# Analog_Sensors.net
KiCad netlist of a schematic drawn in Altium Designer
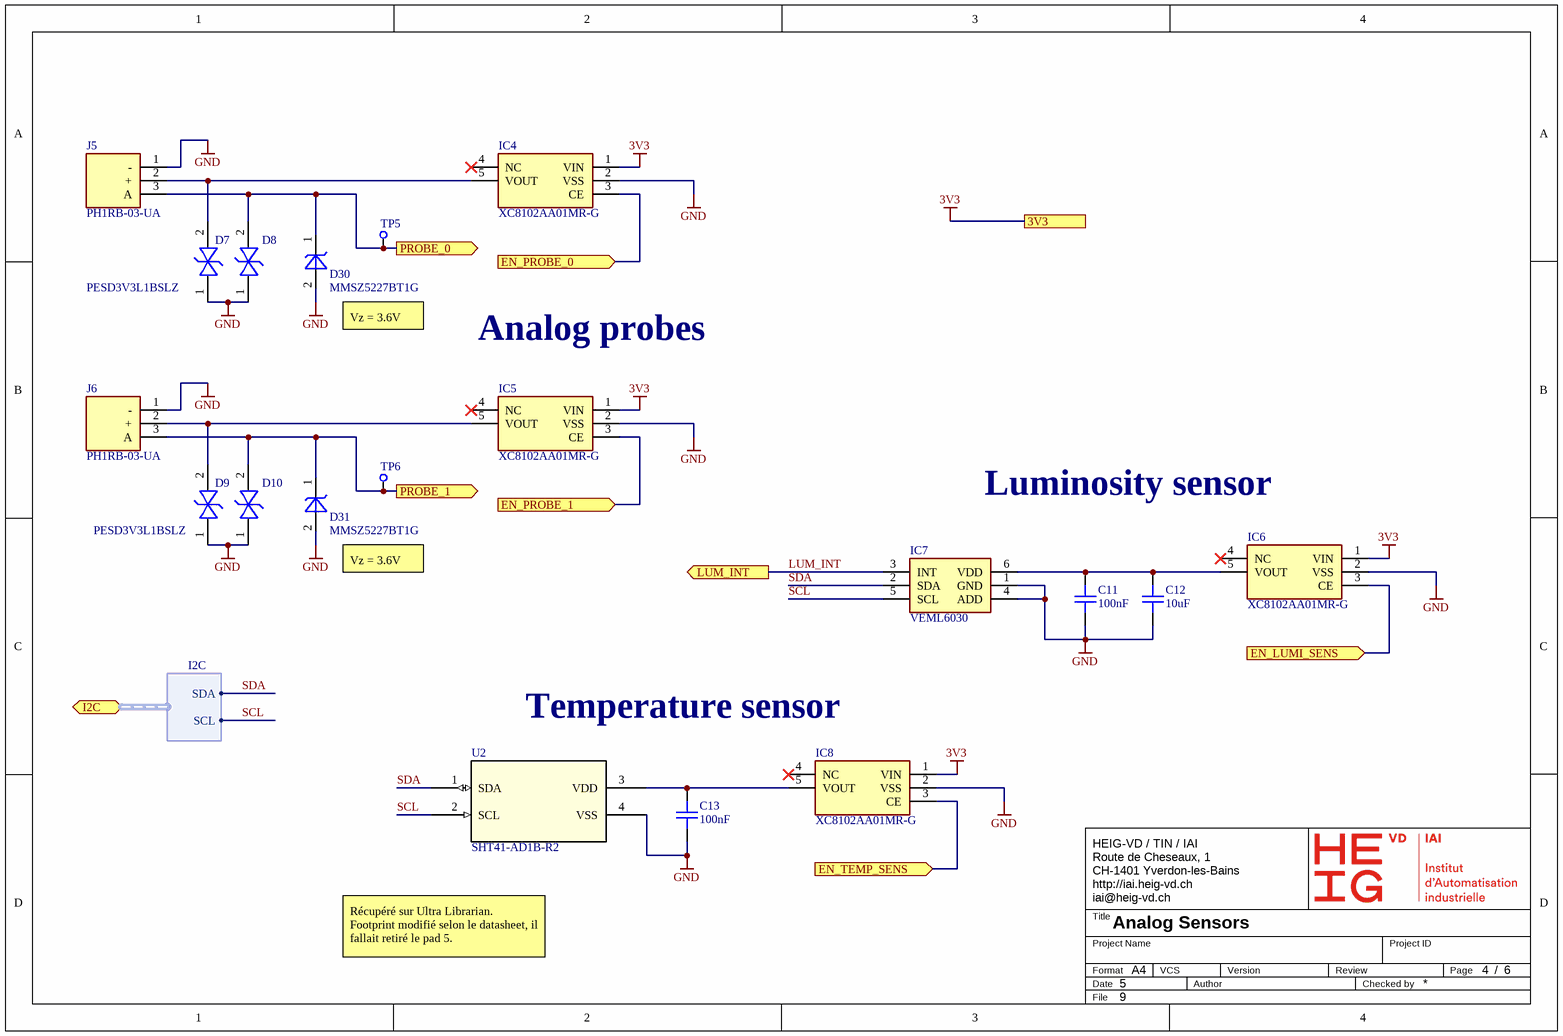
[diagram p0: Analog_Sensors.SchDoc]

(export (version "E")
  (design (tool "Eeschema 10.0.6"))
  (components
    (comp (ref "C11")
      (value "100nF")
      (footprint "CAPC1005X05N")
      (description "100nF 10% 50V Ceramic Capacitor X8L 0402 (1005 Metric)")
      (fields (field (name "TOLERANCE") "10%"))
      (libsource (lib "HEIG-VD Pro") (part "Capacitor"))
    )
    (comp (ref "C12")
      (value "10uF")
      (footprint "CAPC3216X18N")
      (description "10 µF ±10% 50V Ceramic Capacitor X7R 1206 (3216 Metric)")
      (fields (field (name "TOLERANCE") "10%"))
      (libsource (lib "HEIG-VD Pro") (part "Capacitor"))
    )
    (comp (ref "C13")
      (value "100nF")
      (footprint "CAPC1005X05N")
      (description "100nF 10% 50V Ceramic Capacitor X8L 0402 (1005 Metric)")
      (fields (field (name "TOLERANCE") "10%"))
      (libsource (lib "HEIG-VD Pro") (part "Capacitor"))
    )
    (comp (ref "D7")
      (value "PESD3V3L1BSLZ")
      (footprint "PESD3V3L1BSLZ")
      (description "Diode ESD (Bi-directional)")
      (fields (field (name "MOUSER PART NUMBER") "771-PESD3V3L1BSLZ"))
      (libsource (lib "Rainette") (part "PESD3V3L1BSLZ"))
    )
    (comp (ref "D8")
      (value "PESD3V3L1BSLZ")
      (footprint "PESD3V3L1BSLZ")
      (description "Diode ESD (Bi-directional)")
      (fields (field (name "MOUSER PART NUMBER") "771-PESD3V3L1BSLZ"))
      (libsource (lib "Rainette") (part "PESD3V3L1BSLZ"))
    )
    (comp (ref "D9")
      (value "PESD3V3L1BSLZ")
      (footprint "PESD3V3L1BSLZ")
      (description "Diode ESD (Bi-directional)")
      (fields (field (name "MOUSER PART NUMBER") "771-PESD3V3L1BSLZ"))
      (libsource (lib "Rainette") (part "PESD3V3L1BSLZ"))
    )
    (comp (ref "D10")
      (value "PESD3V3L1BSLZ")
      (footprint "PESD3V3L1BSLZ")
      (description "Diode ESD (Bi-directional)")
      (fields (field (name "MOUSER PART NUMBER") "771-PESD3V3L1BSLZ"))
      (libsource (lib "Rainette") (part "PESD3V3L1BSLZ"))
    )
    (comp (ref "D30")
      (value "MMSZ5227BT1G")
      (footprint "SOD3717X135")
      (description "Zener Diode 3.6V 500 mW ±5% Surface Mount SOD-123")
      (fields (field (name "POWER") "500mW") (field (name "TOLERANCE") "5%"))
      (libsource (lib "HEIG-VD iAi") (part "Diode Zener"))
    )
    (comp (ref "D31")
      (value "MMSZ5227BT1G")
      (footprint "SOD3717X135")
      (description "Zener Diode 3.6V 500 mW ±5% Surface Mount SOD-123")
      (fields (field (name "POWER") "500mW") (field (name "TOLERANCE") "5%"))
      (libsource (lib "HEIG-VD iAi") (part "Diode Zener"))
    )
    (comp (ref "IC4")
      (value "XC8102AA01MR-G")
      (footprint "SOT95P280X130-5N")
      (description "Integrated Circuit")
      (fields (field (name "MOUSER PART NUMBER") "865-XC8102AA01MR-G"))
      (libsource (lib "Rainette") (part "XC8102AA01MR-G"))
    )
    (comp (ref "IC5")
      (value "XC8102AA01MR-G")
      (footprint "SOT95P280X130-5N")
      (description "Integrated Circuit")
      (fields (field (name "MOUSER PART NUMBER") "865-XC8102AA01MR-G"))
      (libsource (lib "Rainette") (part "XC8102AA01MR-G"))
    )
    (comp (ref "IC6")
      (value "XC8102AA01MR-G")
      (footprint "SOT95P280X130-5N")
      (description "Integrated Circuit")
      (fields (field (name "MOUSER PART NUMBER") "865-XC8102AA01MR-G"))
      (libsource (lib "Rainette") (part "XC8102AA01MR-G"))
    )
    (comp (ref "IC7")
      (value "VEML6030")
      (footprint "VEML6030")
      (description "Integrated Circuit")
      (fields (field (name "MOUSER PART NUMBER") "78-VEML6030"))
      (libsource (lib "Rainette") (part "VEML6030"))
    )
    (comp (ref "IC8")
      (value "XC8102AA01MR-G")
      (footprint "SOT95P280X130-5N")
      (description "Integrated Circuit")
      (fields (field (name "MOUSER PART NUMBER") "865-XC8102AA01MR-G"))
      (libsource (lib "Rainette") (part "XC8102AA01MR-G"))
    )
    (comp (ref "J5")
      (value "PH1RB-03-UA")
      (footprint "HDRRA3W64P0X254_1X3_762X250X301P")
      (description "Connector")
      (fields (field (name "MOUSER PART NUMBER") "737-PH1RB-03-UA"))
      (libsource (lib "Rainette") (part "PH1RB-03-UA"))
    )
    (comp (ref "J6")
      (value "PH1RB-03-UA")
      (footprint "HDRRA3W64P0X254_1X3_762X250X301P")
      (description "Connector")
      (fields (field (name "MOUSER PART NUMBER") "737-PH1RB-03-UA"))
      (libsource (lib "Rainette") (part "PH1RB-03-UA"))
    )
    (comp (ref "TP5")
      (value "ICT Test Point - TH Round Pad")
      (footprint "TPICTTH09N")
      (description "Through hole test point round pad for in-circuit test")
      (libsource (lib "HEIG-VD Pro") (part "Test Point ICT THT"))
    )
    (comp (ref "TP6")
      (value "ICT Test Point - TH Round Pad")
      (footprint "TPICTTH09N")
      (description "Through hole test point round pad for in-circuit test")
      (libsource (lib "HEIG-VD Pro") (part "Test Point ICT THT"))
    )
    (comp (ref "U2")
      (value "SHT41-AD1B-R2")
      (footprint "DFN4_SHT41_SEN")
      (description "No Description Available")
      (libsource (lib "SHT41-AD1B-R2") (part "SHT41-AD1B-R2"))
    )
  )
  (nets
    (net (code "2") (name "/EN_LUMI_SENS") (class "Default")
      (node (ref "IC6") (pin "3") (pinfunction "CE_3") (pintype "passive"))
    )
    (net (code "3") (name "/EN_PROBE_0") (class "Default")
      (node (ref "IC4") (pin "3") (pinfunction "CE_3") (pintype "passive"))
    )
    (net (code "4") (name "/EN_PROBE_1") (class "Default")
      (node (ref "IC5") (pin "3") (pinfunction "CE_3") (pintype "passive"))
    )
    (net (code "5") (name "/EN_TEMP_SENS") (class "Default")
      (node (ref "IC8") (pin "3") (pinfunction "CE_3") (pintype "passive"))
    )
    (net (code "6") (name "/LUM_INT") (class "Default")
      (node (ref "IC7") (pin "3") (pinfunction "INT_3") (pintype "passive"))
    )
    (net (code "7") (name "/PROBE_0") (class "Default")
      (node (ref "D30") (pin "1") (pinfunction "K_1") (pintype "passive"))
      (node (ref "D8") (pin "2") (pinfunction "K2_2") (pintype "passive"))
      (node (ref "J5") (pin "3") (pinfunction "A_3") (pintype "passive"))
      (node (ref "TP5") (pin "1") (pinfunction "1_1") (pintype "passive"))
    )
    (net (code "8") (name "/PROBE_1") (class "Default")
      (node (ref "D10") (pin "2") (pinfunction "K2_2") (pintype "passive"))
      (node (ref "D31") (pin "1") (pinfunction "K_1") (pintype "passive"))
      (node (ref "J6") (pin "3") (pinfunction "A_3") (pintype "passive"))
      (node (ref "TP6") (pin "1") (pinfunction "1_1") (pintype "passive"))
    )
    (net (code "9") (name "/SCL") (class "Default")
      (node (ref "IC7") (pin "5") (pinfunction "SCL_5") (pintype "passive"))
      (node (ref "U2") (pin "2") (pinfunction "SCL_2") (pintype "input"))
    )
    (net (code "10") (name "/SDA") (class "Default")
      (node (ref "IC7") (pin "2") (pinfunction "SDA_2") (pintype "passive"))
      (node (ref "U2") (pin "1") (pinfunction "SDA_1") (pintype "bidirectional"))
    )
    (net (code "12") (name "3V3") (class "Default")
      (node (ref "IC4") (pin "1") (pinfunction "VIN_1") (pintype "passive"))
      (node (ref "IC5") (pin "1") (pinfunction "VIN_1") (pintype "passive"))
      (node (ref "IC6") (pin "1") (pinfunction "VIN_1") (pintype "passive"))
      (node (ref "IC8") (pin "1") (pinfunction "VIN_1") (pintype "passive"))
    )
    (net (code "13") (name "GND") (class "Default")
      (node (ref "C11") (pin "2") (pinfunction "2_2") (pintype "passive"))
      (node (ref "C12") (pin "1") (pinfunction "1_1") (pintype "passive"))
      (node (ref "C13") (pin "2") (pinfunction "2_2") (pintype "passive"))
      (node (ref "D10") (pin "1") (pinfunction "K1_1") (pintype "passive"))
      (node (ref "D30") (pin "2") (pinfunction "A_2") (pintype "passive"))
      (node (ref "D31") (pin "2") (pinfunction "A_2") (pintype "passive"))
      (node (ref "D7") (pin "1") (pinfunction "K1_1") (pintype "passive"))
      (node (ref "D8") (pin "1") (pinfunction "K1_1") (pintype "passive"))
      (node (ref "D9") (pin "1") (pinfunction "K1_1") (pintype "passive"))
      (node (ref "IC4") (pin "2") (pinfunction "VSS_2") (pintype "passive"))
      (node (ref "IC5") (pin "2") (pinfunction "VSS_2") (pintype "passive"))
      (node (ref "IC6") (pin "2") (pinfunction "VSS_2") (pintype "passive"))
      (node (ref "IC7") (pin "1") (pinfunction "GND_1") (pintype "passive"))
      (node (ref "IC7") (pin "4") (pinfunction "ADD_4") (pintype "passive"))
      (node (ref "IC8") (pin "2") (pinfunction "VSS_2") (pintype "passive"))
      (node (ref "J5") (pin "1") (pinfunction "-_1") (pintype "passive"))
      (node (ref "J6") (pin "1") (pinfunction "-_1") (pintype "passive"))
      (node (ref "U2") (pin "4") (pinfunction "VSS_4") (pintype "power_in"))
    )
    (net (code "14") (name "Net-(D7-K2)") (class "Default")
      (node (ref "D7") (pin "2") (pinfunction "K2_2") (pintype "passive"))
      (node (ref "IC4") (pin "5") (pinfunction "VOUT_5") (pintype "passive"))
      (node (ref "J5") (pin "2") (pinfunction "+_2") (pintype "passive"))
    )
    (net (code "15") (name "Net-(D9-K2)") (class "Default")
      (node (ref "D9") (pin "2") (pinfunction "K2_2") (pintype "passive"))
      (node (ref "IC5") (pin "5") (pinfunction "VOUT_5") (pintype "passive"))
      (node (ref "J6") (pin "2") (pinfunction "+_2") (pintype "passive"))
    )
    (net (code "16") (name "Net-(IC6-VOUT)") (class "Default")
      (node (ref "C11") (pin "1") (pinfunction "1_1") (pintype "passive"))
      (node (ref "C12") (pin "2") (pinfunction "2_2") (pintype "passive"))
      (node (ref "IC6") (pin "5") (pinfunction "VOUT_5") (pintype "passive"))
      (node (ref "IC7") (pin "6") (pinfunction "VDD_6") (pintype "passive"))
    )
    (net (code "17") (name "Net-(IC8-VOUT)") (class "Default")
      (node (ref "C13") (pin "1") (pinfunction "1_1") (pintype "passive"))
      (node (ref "IC8") (pin "5") (pinfunction "VOUT_5") (pintype "passive"))
      (node (ref "U2") (pin "3") (pinfunction "VDD_3") (pintype "power_in"))
    )
    (net (code "18") (name "unconnected-(IC4-NC-Pad4)") (class "Default")
      (node (ref "IC4") (pin "4") (pinfunction "NC_4") (pintype "passive+no_connect"))
    )
    (net (code "19") (name "unconnected-(IC5-NC-Pad4)") (class "Default")
      (node (ref "IC5") (pin "4") (pinfunction "NC_4") (pintype "passive+no_connect"))
    )
    (net (code "20") (name "unconnected-(IC6-NC-Pad4)") (class "Default")
      (node (ref "IC6") (pin "4") (pinfunction "NC_4") (pintype "passive+no_connect"))
    )
    (net (code "21") (name "unconnected-(IC8-NC-Pad4)") (class "Default")
      (node (ref "IC8") (pin "4") (pinfunction "NC_4") (pintype "passive+no_connect"))
    )
  )
)
